# LED_Sensor.net
KiCad netlist of a schematic drawn in Altium Designer
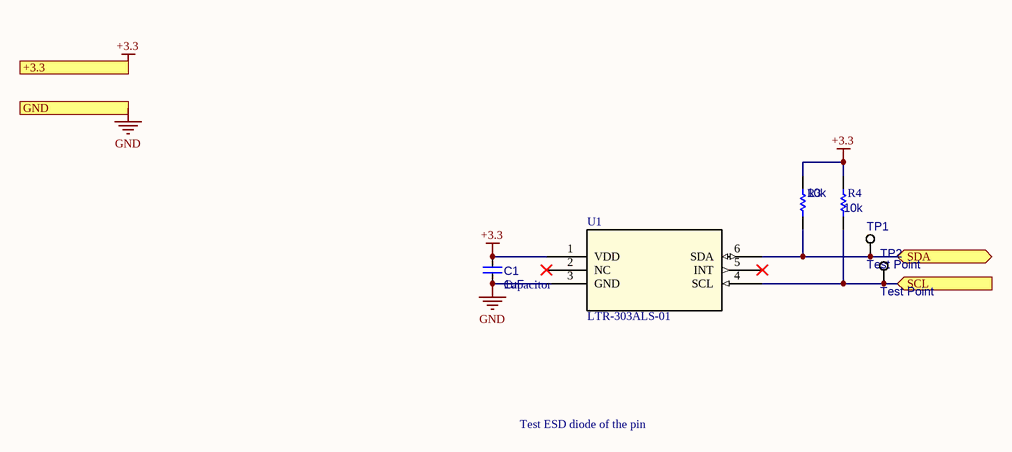
[diagram p0: LED_Sensor.SchDoc]

(export (version "E")
  (design (tool "Eeschema 10.0.6"))
  (components
    (comp (ref "C1")
      (value "Capacitor")
      (footprint "C0603B")
      (description "Non-polarized capacitor")
      (fields (field (name "ALTIUM_VALUE") "1uF"))
      (libsource (lib "Space Concordia") (part "Capacitor"))
    )
    (comp (ref "R3")
      (value "10k")
      (footprint "R0603B")
      (description "Resistor")
      (libsource (lib "Space Concordia") (part "Resistor"))
    )
    (comp (ref "R4")
      (value "10k")
      (footprint "R0603B")
      (description "Resistor")
      (libsource (lib "Space Concordia") (part "Resistor"))
    )
    (comp (ref "TP1")
      (value "Test Point")
      (footprint "TP-TH")
      (description "In circuit test point for a net")
      (libsource (lib "Space Concordia") (part "Test Point"))
    )
    (comp (ref "TP2")
      (value "Test Point")
      (footprint "TP-TH")
      (description "In circuit test point for a net")
      (libsource (lib "Space Concordia") (part "Test Point"))
    )
    (comp (ref "U1")
      (value "LTR-303ALS-01")
      (footprint "LTR-303ALS-01_LTO")
      (description "No Description Available")
      (libsource (lib "Space Concordia") (part "LTR-303ALS-01"))
    )
  )
  (nets
    (net (code "1") (name "+3.3") (class "Default")
      (node (ref "C1") (pin "2") (pinfunction "2_2") (pintype "passive"))
      (node (ref "R3") (pin "2") (pinfunction "2_2") (pintype "passive"))
      (node (ref "R4") (pin "2") (pinfunction "2_2") (pintype "passive"))
      (node (ref "U1") (pin "1") (pinfunction "VDD_1") (pintype "power_in"))
    )
    (net (code "2") (name "/SCL") (class "Default")
      (node (ref "R4") (pin "1") (pinfunction "1_1") (pintype "passive"))
      (node (ref "TP2") (pin "1") (pinfunction "Pad_1") (pintype "passive"))
      (node (ref "U1") (pin "4") (pinfunction "SCL_4") (pintype "input"))
    )
    (net (code "3") (name "/SDA") (class "Default")
      (node (ref "R3") (pin "1") (pinfunction "1_1") (pintype "passive"))
      (node (ref "TP1") (pin "1") (pinfunction "Pad_1") (pintype "passive"))
      (node (ref "U1") (pin "6") (pinfunction "SDA_6") (pintype "bidirectional"))
    )
    (net (code "4") (name "GND") (class "Default")
      (node (ref "C1") (pin "1") (pinfunction "1_1") (pintype "passive"))
      (node (ref "U1") (pin "3") (pinfunction "GND_3") (pintype "power_in"))
    )
    (net (code "5") (name "unconnected-(U1-INT-Pad5)") (class "Default")
      (node (ref "U1") (pin "5") (pinfunction "INT_5") (pintype "output+no_connect"))
    )
    (net (code "6") (name "unconnected-(U1-NC-Pad2)") (class "Default")
      (node (ref "U1") (pin "2") (pinfunction "NC_2") (pintype "passive+no_connect"))
    )
  )
)
